# SuperCap_UPS.net
KiCad netlist of a schematic drawn in Altium Designer
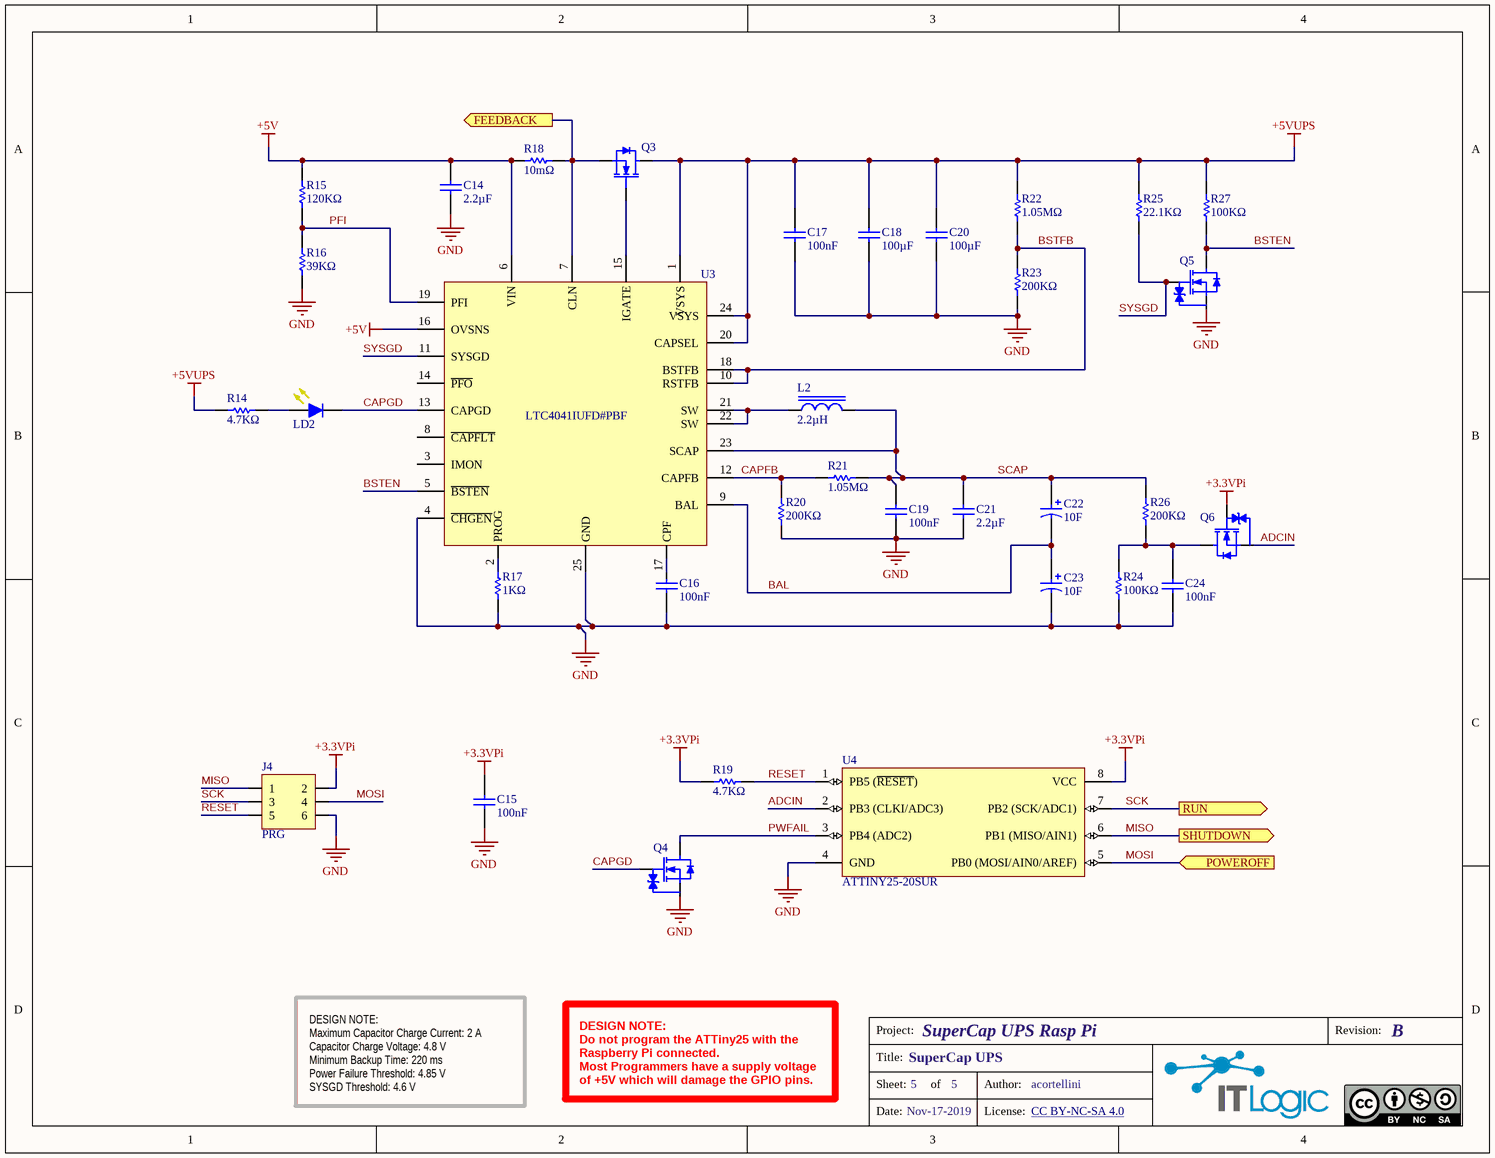
[diagram p0: SuperCap UPS.SchDoc]

(export (version "E")
  (design (tool "Eeschema 10.0.6"))
  (components
    (comp (ref "C14")
      (value "2.2µF")
      (footprint "C0805-H140")
      (description "Cap 0805 Case Ceramic 2.2uF 16V X7R 10%")
      (fields
        (field (name "MANUFACTURER") "KEMET")
        (field (name "MANUFACTURER PART NUMBER") "C0805C225K4RACTU")
      )
      (libsource (lib "IT Logic Library") (part "C0805C225K4RACTU"))
    )
    (comp (ref "C15")
      (value "100nF")
      (footprint "C0805-H10")
      (description "Cap 0805 Case Ceramic 100nF 50V X7R")
      (fields
        (field (name "MANUFACTURER") "KEMET")
        (field (name "MANUFACTURER PART NUMBER") "C0805C104K5RACTU")
      )
      (libsource (lib "IT Logic Library") (part "C0805C104K5RACTU"))
    )
    (comp (ref "C16")
      (value "100nF")
      (footprint "C0805-H10")
      (description "Cap 0805 Case Ceramic 100nF 50V X7R")
      (fields
        (field (name "MANUFACTURER") "KEMET")
        (field (name "MANUFACTURER PART NUMBER") "C0805C104K5RACTU")
      )
      (libsource (lib "IT Logic Library") (part "C0805C104K5RACTU"))
    )
    (comp (ref "C17")
      (value "100nF")
      (footprint "C0805-H10")
      (description "Cap 0805 Case Ceramic 100nF 50V X7R")
      (fields
        (field (name "MANUFACTURER") "KEMET")
        (field (name "MANUFACTURER PART NUMBER") "C0805C104K5RACTU")
      )
      (libsource (lib "IT Logic Library") (part "C0805C104K5RACTU"))
    )
    (comp (ref "C18")
      (value "100µF")
      (footprint "C1210-H250")
      (description "Cap 1210 Case Ceramic 100uF 10V X5S 20%")
      (fields
        (field (name "MANUFACTURER") "Murata")
        (field (name "MANUFACTURER PART NUMBER") "GRM32ER61A107ME20L")
      )
      (libsource (lib "IT Logic Library") (part "GRM32ER61A107ME20L"))
    )
    (comp (ref "C19")
      (value "100nF")
      (footprint "C0805-H10")
      (description "Cap 0805 Case Ceramic 100nF 50V X7R")
      (fields
        (field (name "MANUFACTURER") "KEMET")
        (field (name "MANUFACTURER PART NUMBER") "C0805C104K5RACTU")
      )
      (libsource (lib "IT Logic Library") (part "C0805C104K5RACTU"))
    )
    (comp (ref "C20")
      (value "100µF")
      (footprint "C1210-H250")
      (description "Cap 1210 Case Ceramic 100uF 10V X5S 20%")
      (fields
        (field (name "MANUFACTURER") "Murata")
        (field (name "MANUFACTURER PART NUMBER") "GRM32ER61A107ME20L")
      )
      (libsource (lib "IT Logic Library") (part "GRM32ER61A107ME20L"))
    )
    (comp (ref "C21")
      (value "2.2µF")
      (footprint "C0805-H140")
      (description "Cap 0805 Case Ceramic 2.2uF 16V X7R 10%")
      (fields
        (field (name "MANUFACTURER") "KEMET")
        (field (name "MANUFACTURER PART NUMBER") "C0805C225K4RACTU")
      )
      (libsource (lib "IT Logic Library") (part "C0805C225K4RACTU"))
    )
    (comp (ref "C22")
      (value "10F")
      (footprint "C-SCCT20B106PRB-ORIZ")
      (description "Cap Super 10F 3.0V (20 X 12.5mm) ESR 50mOhm")
      (fields (field (name "MANUFACTURER") "AVX") (field (name "MANUFACTURER PART NUMBER") "SCCT20E106SRB"))
      (libsource (lib "IT Logic Library") (part "SCCT20E106SRB"))
    )
    (comp (ref "C23")
      (value "10F")
      (footprint "C-SCCT20B106PRB-ORIZ")
      (description "Cap Super 10F 3.0V (20 X 12.5mm) ESR 50mOhm")
      (fields (field (name "MANUFACTURER") "AVX") (field (name "MANUFACTURER PART NUMBER") "SCCT20E106SRB"))
      (libsource (lib "IT Logic Library") (part "SCCT20E106SRB"))
    )
    (comp (ref "C24")
      (value "100nF")
      (footprint "C0805-H10")
      (description "Cap 0805 Case Ceramic 100nF 50V X7R")
      (fields
        (field (name "MANUFACTURER") "KEMET")
        (field (name "MANUFACTURER PART NUMBER") "C0805C104K5RACTU")
      )
      (libsource (lib "IT Logic Library") (part "C0805C104K5RACTU"))
    )
    (comp (ref "J4")
      (value "PRG")
      (footprint "HDR-V-2R-03P-5.8L")
      (description "Breakaway Header Vert - 2 Row - 3 Pos - 6 mm Lenght - Gold")
      (fields
        (field (name "MANUFACTURER") "TE Connectivity")
        (field (name "MANUFACTURER PART NUMBER") "5-146256-3")
      )
      (libsource (lib "IT Logic Library") (part "5-146256-3"))
    )
    (comp (ref "L2")
      (value "2.2µH")
      (footprint "IND-XAL5030")
      (description "Inductor Power SRP6540 Series, 2.2uH, 9.7A,  Shielded, 0.0132 ohm, SMD")
      (fields
        (field (name "MANUFACTURER") "Coilcraft")
        (field (name "MANUFACTURER PART NUMBER") "XAL5030-222MEB")
      )
      (libsource (lib "IT Logic Library") (part "XAL5030-222MEB"))
    )
    (comp (ref "LD2")
      (value "LTST-S220KSKT")
      (footprint "LED-0805-Y-SIDE")
      (description "LED 0805 Side Yellow 588nm 2-Pin")
      (fields (field (name "MANUFACTURER") "Vishay Lite-On"))
      (libsource (lib "IT Logic Library") (part "LTST-S220KSKT"))
    )
    (comp (ref "Q3")
      (value "SISA88DN-T1-GE3")
      (footprint "POWERPAK-1212-8-S")
      (description "Mosfet 30V Vds 20V Vgs 5.4mOhm PowerPAK 1212-8")
      (fields (field (name "MANUFACTURER") "Vishay"))
      (libsource (lib "IT Logic Library") (part "SISA88DN-T1-GE3"))
    )
    (comp (ref "Q4")
      (value "BSS138K-13")
      (footprint "SOT-23")
      (description "Mosfet N 50V Vds 20V Vgs ESD 1.4R SOT-23")
      (fields (field (name "MANUFACTURER") "Diodes"))
      (libsource (lib "IT Logic Library") (part "BSS138K-13"))
    )
    (comp (ref "Q5")
      (value "BSS138K-13")
      (footprint "SOT-23")
      (description "Mosfet N 50V Vds 20V Vgs ESD 1.4R SOT-23")
      (fields (field (name "MANUFACTURER") "Diodes"))
      (libsource (lib "IT Logic Library") (part "BSS138K-13"))
    )
    (comp (ref "Q6")
      (value "BSS138K-13")
      (footprint "SOT-23")
      (description "Mosfet N 50V Vds 20V Vgs ESD 1.4R SOT-23")
      (fields (field (name "MANUFACTURER") "Diodes"))
      (libsource (lib "IT Logic Library") (part "BSS138K-13"))
    )
    (comp (ref "R14")
      (value "4.7KΩ")
      (footprint "R0805-H60")
      (description "Resistor 0805 Case 4.7KR 1% 1/8W")
      (fields
        (field (name "MANUFACTURER") "Yageo")
        (field (name "MANUFACTURER PART NUMBER") "RC0805FR-074K7L")
      )
      (libsource (lib "IT Logic Library") (part "RC0805FR-074K7L"))
    )
    (comp (ref "R15")
      (value "120KΩ")
      (footprint "R0805-H60")
      (description "Resistor 0805 Case 120KR 1% 1/8W")
      (fields
        (field (name "MANUFACTURER") "Yageo")
        (field (name "MANUFACTURER PART NUMBER") "RC0805FR-07120KL")
      )
      (libsource (lib "IT Logic Library") (part "RC0805FR-07120KL"))
    )
    (comp (ref "R16")
      (value "39KΩ")
      (footprint "R0805-H60")
      (description "Resistor 0805 Case 39KR 1% 1/8W")
      (fields
        (field (name "MANUFACTURER") "Yageo")
        (field (name "MANUFACTURER PART NUMBER") "RC0805FR-0739KL")
      )
      (libsource (lib "IT Logic Library") (part "RC0805FR-0739KL"))
    )
    (comp (ref "R17")
      (value "1KΩ")
      (footprint "R0805-H60")
      (description "Resistor 0805 Case 1KR 1% 1/8W")
      (fields
        (field (name "MANUFACTURER") "Yageo")
        (field (name "MANUFACTURER PART NUMBER") "RC0805FR-071KL")
      )
      (libsource (lib "IT Logic Library") (part "RC0805FR-071KL"))
    )
    (comp (ref "R18")
      (value "10mΩ")
      (footprint "R0508-H60")
      (description "Resistor 0508 Case 10mR 1% 1/2W Current Sense")
      (fields
        (field (name "MANUFACTURER") "Susumu")
        (field (name "MANUFACTURER PART NUMBER") "KRL2012E-M-R010-F-T5")
      )
      (libsource (lib "IT Logic Library") (part "KRL2012E-M-R010-F-T5"))
    )
    (comp (ref "R19")
      (value "4.7KΩ")
      (footprint "R0805-H60")
      (description "Resistor 0805 Case 4.7KR 1% 1/8W")
      (fields
        (field (name "MANUFACTURER") "Yageo")
        (field (name "MANUFACTURER PART NUMBER") "RC0805FR-074K7L")
      )
      (libsource (lib "IT Logic Library") (part "RC0805FR-074K7L"))
    )
    (comp (ref "R20")
      (value "200KΩ")
      (footprint "R0805-H60")
      (description "Resistor 0805 Case 200KR 1% 1/8W")
      (fields
        (field (name "MANUFACTURER") "Yageo")
        (field (name "MANUFACTURER PART NUMBER") "RC0805FR-07200KL")
      )
      (libsource (lib "IT Logic Library") (part "RC0805FR-07200KL"))
    )
    (comp (ref "R21")
      (value "1.05MΩ")
      (footprint "R0805-H60")
      (description "Resistor 0805 Case 1.05MR 1% 1/8W")
      (fields
        (field (name "MANUFACTURER") "Yageo")
        (field (name "MANUFACTURER PART NUMBER") "RC0805FR-071M05L")
      )
      (libsource (lib "IT Logic Library") (part "RC0805FR-071M05L"))
    )
    (comp (ref "R22")
      (value "1.05MΩ")
      (footprint "R0805-H60")
      (description "Resistor 0805 Case 1.05MR 1% 1/8W")
      (fields
        (field (name "MANUFACTURER") "Yageo")
        (field (name "MANUFACTURER PART NUMBER") "RC0805FR-071M05L")
      )
      (libsource (lib "IT Logic Library") (part "RC0805FR-071M05L"))
    )
    (comp (ref "R23")
      (value "200KΩ")
      (footprint "R0805-H60")
      (description "Resistor 0805 Case 200KR 1% 1/8W")
      (fields
        (field (name "MANUFACTURER") "Yageo")
        (field (name "MANUFACTURER PART NUMBER") "RC0805FR-07200KL")
      )
      (libsource (lib "IT Logic Library") (part "RC0805FR-07200KL"))
    )
    (comp (ref "R24")
      (value "100KΩ")
      (footprint "R0805-H60")
      (description "Resistor 0805 Case 100KR 1% 1/8W")
      (fields
        (field (name "MANUFACTURER") "Yageo")
        (field (name "MANUFACTURER PART NUMBER") "RC0805FR-07100KL")
      )
      (libsource (lib "IT Logic Library") (part "RC0805FR-07100KL"))
    )
    (comp (ref "R25")
      (value "22.1KΩ")
      (footprint "R0805-H60")
      (description "Resistor 0805 Case 22.1KR 1% 1/8W")
      (fields
        (field (name "MANUFACTURER") "Yageo")
        (field (name "MANUFACTURER PART NUMBER") "RC0805FR-0722K1L")
      )
      (libsource (lib "IT Logic Library") (part "RC0805FR-0722K1L"))
    )
    (comp (ref "R26")
      (value "200KΩ")
      (footprint "R0805-H60")
      (description "Resistor 0805 Case 200KR 1% 1/8W")
      (fields
        (field (name "MANUFACTURER") "Yageo")
        (field (name "MANUFACTURER PART NUMBER") "RC0805FR-07200KL")
      )
      (libsource (lib "IT Logic Library") (part "RC0805FR-07200KL"))
    )
    (comp (ref "R27")
      (value "100KΩ")
      (footprint "R0805-H60")
      (description "Resistor 0805 Case 100KR 1% 1/8W")
      (fields
        (field (name "MANUFACTURER") "Yageo")
        (field (name "MANUFACTURER PART NUMBER") "RC0805FR-07100KL")
      )
      (libsource (lib "IT Logic Library") (part "RC0805FR-07100KL"))
    )
    (comp (ref "U3")
      (value "LTC4041IUFD#PBF")
      (footprint "QFN-50x40-24-THP")
      (description "Power Management 2.5A Supercapacitor Backup Buck Converter and Charger")
      (fields (field (name "MANUFACTURER") "Analog Devices"))
      (libsource (lib "IT Logic Library") (part "LTC4041IUFD#PBF"))
    )
    (comp (ref "U4")
      (value "ATTINY25-20SUR")
      (footprint "SOIC-8-W")
      (description "AVR MCU8-bit ATTiny - 2kB Flash 0.128kB EEPROM 6 I/O Pins - SOIC-8-W")
      (fields (field (name "MANUFACTURER") "Microchip"))
      (libsource (lib "IT Logic Library") (part "ATTINY25-20SUR"))
    )
  )
  (nets
    (net (code "1") (name "+3.3VPi") (class "Default")
      (node (ref "C15") (pin "2") (pinfunction "2_2") (pintype "passive"))
      (node (ref "J4") (pin "2") (pinfunction "2_2") (pintype "passive"))
      (node (ref "Q6") (pin "1") (pinfunction "G_1") (pintype "passive"))
      (node (ref "R19") (pin "1") (pinfunction "1_1") (pintype "passive"))
      (node (ref "U4") (pin "8") (pinfunction "VCC_8") (pintype "power_in"))
    )
    (net (code "2") (name "+5V") (class "Default")
      (node (ref "C14") (pin "2") (pinfunction "2_2") (pintype "passive"))
      (node (ref "R15") (pin "2") (pinfunction "2_2") (pintype "passive"))
      (node (ref "R18") (pin "1") (pinfunction "1_1") (pintype "passive"))
      (node (ref "U3") (pin "16") (pinfunction "OVSNS_16") (pintype "passive"))
      (node (ref "U3") (pin "6") (pinfunction "VIN_6") (pintype "passive"))
    )
    (net (code "3") (name "+5VUPS") (class "Default")
      (node (ref "C17") (pin "2") (pinfunction "2_2") (pintype "passive"))
      (node (ref "C18") (pin "2") (pinfunction "2_2") (pintype "passive"))
      (node (ref "C20") (pin "2") (pinfunction "2_2") (pintype "passive"))
      (node (ref "Q3") (pin "3") (pinfunction "D_3") (pintype "passive"))
      (node (ref "R14") (pin "1") (pinfunction "1_1") (pintype "passive"))
      (node (ref "R22") (pin "2") (pinfunction "2_2") (pintype "passive"))
      (node (ref "R25") (pin "2") (pinfunction "2_2") (pintype "passive"))
      (node (ref "R27") (pin "2") (pinfunction "2_2") (pintype "passive"))
      (node (ref "U3") (pin "1") (pinfunction "VSYS_1") (pintype "passive"))
      (node (ref "U3") (pin "20") (pinfunction "CAPSEL_20") (pintype "passive"))
      (node (ref "U3") (pin "24") (pinfunction "VSYS_24") (pintype "passive"))
    )
    (net (code "4") (name "/ADCIN") (class "Default")
      (node (ref "Q6") (pin "2") (pinfunction "S_2") (pintype "passive"))
      (node (ref "U4") (pin "2") (pinfunction "PB3_(CLKI/ADC3)_2") (pintype "bidirectional"))
    )
    (net (code "5") (name "/BAL") (class "Default")
      (node (ref "C22") (pin "2") (pinfunction "2_2") (pintype "passive"))
      (node (ref "C23") (pin "1") (pinfunction "1_1") (pintype "passive"))
      (node (ref "U3") (pin "9") (pinfunction "BAL_9") (pintype "passive"))
    )
    (net (code "6") (name "/BSTEN") (class "Default")
      (node (ref "Q5") (pin "3") (pinfunction "D_3") (pintype "passive"))
      (node (ref "R27") (pin "1") (pinfunction "1_1") (pintype "passive"))
      (node (ref "U3") (pin "5") (pinfunction "~{BSTEN}_5") (pintype "passive"))
    )
    (net (code "7") (name "/BSTFB") (class "Default")
      (node (ref "R22") (pin "1") (pinfunction "1_1") (pintype "passive"))
      (node (ref "R23") (pin "2") (pinfunction "2_2") (pintype "passive"))
      (node (ref "U3") (pin "10") (pinfunction "RSTFB_10") (pintype "passive"))
      (node (ref "U3") (pin "18") (pinfunction "BSTFB_18") (pintype "passive"))
    )
    (net (code "8") (name "/CAPFB") (class "Default")
      (node (ref "R20") (pin "2") (pinfunction "2_2") (pintype "passive"))
      (node (ref "R21") (pin "1") (pinfunction "1_1") (pintype "passive"))
      (node (ref "U3") (pin "12") (pinfunction "CAPFB_12") (pintype "passive"))
    )
    (net (code "9") (name "/CAPGD") (class "Default")
      (node (ref "LD2") (pin "1") (pinfunction "K_1") (pintype "passive"))
      (node (ref "Q4") (pin "1") (pinfunction "G_1") (pintype "passive"))
      (node (ref "U3") (pin "13") (pinfunction "CAPGD_13") (pintype "passive"))
    )
    (net (code "10") (name "/FEEDBACK") (class "Default")
      (node (ref "Q3") (pin "1") (pinfunction "S_1") (pintype "passive"))
      (node (ref "R18") (pin "2") (pinfunction "2_2") (pintype "passive"))
      (node (ref "U3") (pin "7") (pinfunction "CLN_7") (pintype "passive"))
    )
    (net (code "11") (name "/MISO") (class "Default")
      (node (ref "J4") (pin "1") (pinfunction "1_1") (pintype "passive"))
      (node (ref "U4") (pin "6") (pinfunction "PB1_(MISO/AIN1)_6") (pintype "bidirectional"))
    )
    (net (code "12") (name "/MOSI") (class "Default")
      (node (ref "J4") (pin "4") (pinfunction "4_4") (pintype "passive"))
      (node (ref "U4") (pin "5") (pinfunction "PB0_(MOSI/AIN0/AREF)_5") (pintype "bidirectional"))
    )
    (net (code "13") (name "/PFI") (class "Default")
      (node (ref "R15") (pin "1") (pinfunction "1_1") (pintype "passive"))
      (node (ref "R16") (pin "2") (pinfunction "2_2") (pintype "passive"))
      (node (ref "U3") (pin "19") (pinfunction "PFI_19") (pintype "passive"))
    )
    (net (code "14") (name "/PWFAIL") (class "Default")
      (node (ref "Q4") (pin "3") (pinfunction "D_3") (pintype "passive"))
      (node (ref "U4") (pin "3") (pinfunction "PB4_(ADC2)_3") (pintype "bidirectional"))
    )
    (net (code "15") (name "/RESET") (class "Default")
      (node (ref "J4") (pin "5") (pinfunction "5_5") (pintype "passive"))
      (node (ref "R19") (pin "2") (pinfunction "2_2") (pintype "passive"))
      (node (ref "U4") (pin "1") (pinfunction "PB5_(~{RESET})_1") (pintype "bidirectional"))
    )
    (net (code "16") (name "/SCAP") (class "Default")
      (node (ref "C19") (pin "2") (pinfunction "2_2") (pintype "passive"))
      (node (ref "C21") (pin "2") (pinfunction "2_2") (pintype "passive"))
      (node (ref "C22") (pin "1") (pinfunction "1_1") (pintype "passive"))
      (node (ref "L2") (pin "2") (pinfunction "2_2") (pintype "passive"))
      (node (ref "R21") (pin "2") (pinfunction "2_2") (pintype "passive"))
      (node (ref "R26") (pin "2") (pinfunction "2_2") (pintype "passive"))
      (node (ref "U3") (pin "23") (pinfunction "SCAP_23") (pintype "passive"))
    )
    (net (code "17") (name "/SCK") (class "Default")
      (node (ref "J4") (pin "3") (pinfunction "3_3") (pintype "passive"))
      (node (ref "U4") (pin "7") (pinfunction "PB2_(SCK/ADC1)_7") (pintype "bidirectional"))
    )
    (net (code "18") (name "/SYSGD") (class "Default")
      (node (ref "Q5") (pin "1") (pinfunction "G_1") (pintype "passive"))
      (node (ref "R25") (pin "1") (pinfunction "1_1") (pintype "passive"))
      (node (ref "U3") (pin "11") (pinfunction "SYSGD_11") (pintype "passive"))
    )
    (net (code "19") (name "GND") (class "Default")
      (node (ref "C14") (pin "1") (pinfunction "1_1") (pintype "passive"))
      (node (ref "C15") (pin "1") (pinfunction "1_1") (pintype "passive"))
      (node (ref "C16") (pin "1") (pinfunction "1_1") (pintype "passive"))
      (node (ref "C17") (pin "1") (pinfunction "1_1") (pintype "passive"))
      (node (ref "C18") (pin "1") (pinfunction "1_1") (pintype "passive"))
      (node (ref "C19") (pin "1") (pinfunction "1_1") (pintype "passive"))
      (node (ref "C20") (pin "1") (pinfunction "1_1") (pintype "passive"))
      (node (ref "C21") (pin "1") (pinfunction "1_1") (pintype "passive"))
      (node (ref "C23") (pin "2") (pinfunction "2_2") (pintype "passive"))
      (node (ref "C24") (pin "1") (pinfunction "1_1") (pintype "passive"))
      (node (ref "J4") (pin "6") (pinfunction "6_6") (pintype "passive"))
      (node (ref "Q4") (pin "2") (pinfunction "S_2") (pintype "passive"))
      (node (ref "Q5") (pin "2") (pinfunction "S_2") (pintype "passive"))
      (node (ref "R16") (pin "1") (pinfunction "1_1") (pintype "passive"))
      (node (ref "R17") (pin "1") (pinfunction "1_1") (pintype "passive"))
      (node (ref "R20") (pin "1") (pinfunction "1_1") (pintype "passive"))
      (node (ref "R23") (pin "1") (pinfunction "1_1") (pintype "passive"))
      (node (ref "R24") (pin "1") (pinfunction "1_1") (pintype "passive"))
      (node (ref "U3") (pin "25") (pinfunction "GND_25") (pintype "passive"))
      (node (ref "U3") (pin "4") (pinfunction "~{CHGEN}_4") (pintype "passive"))
      (node (ref "U4") (pin "4") (pinfunction "GND_4") (pintype "power_in"))
    )
    (net (code "20") (name "Net-(L2-Pad1)") (class "Default")
      (node (ref "L2") (pin "1") (pinfunction "1_1") (pintype "passive"))
      (node (ref "U3") (pin "21") (pinfunction "SW_21") (pintype "passive"))
      (node (ref "U3") (pin "22") (pinfunction "SW_22") (pintype "passive"))
    )
    (net (code "21") (name "Net-(LD2-A)") (class "Default")
      (node (ref "LD2") (pin "2") (pinfunction "A_2") (pintype "passive"))
      (node (ref "R14") (pin "2") (pinfunction "2_2") (pintype "passive"))
    )
    (net (code "22") (name "Net-(Q3-G)") (class "Default")
      (node (ref "Q3") (pin "2") (pinfunction "G_2") (pintype "passive"))
      (node (ref "U3") (pin "15") (pinfunction "IGATE_15") (pintype "passive"))
    )
    (net (code "23") (name "Net-(Q6-D)") (class "Default")
      (node (ref "C24") (pin "2") (pinfunction "2_2") (pintype "passive"))
      (node (ref "Q6") (pin "3") (pinfunction "D_3") (pintype "passive"))
      (node (ref "R24") (pin "2") (pinfunction "2_2") (pintype "passive"))
      (node (ref "R26") (pin "1") (pinfunction "1_1") (pintype "passive"))
    )
    (net (code "24") (name "Net-(U3-CPF)") (class "Default")
      (node (ref "C16") (pin "2") (pinfunction "2_2") (pintype "passive"))
      (node (ref "U3") (pin "17") (pinfunction "CPF_17") (pintype "passive"))
    )
    (net (code "25") (name "Net-(U3-PROG)") (class "Default")
      (node (ref "R17") (pin "2") (pinfunction "2_2") (pintype "passive"))
      (node (ref "U3") (pin "2") (pinfunction "PROG_2") (pintype "passive"))
    )
    (net (code "26") (name "unconnected-(U3-IMON-Pad3)") (class "Default")
      (node (ref "U3") (pin "3") (pinfunction "IMON_3") (pintype "passive"))
    )
    (net (code "27") (name "unconnected-(U3-~{CAPFLT}-Pad8)") (class "Default")
      (node (ref "U3") (pin "8") (pinfunction "~{CAPFLT}_8") (pintype "passive"))
    )
    (net (code "28") (name "unconnected-(U3-~{PFO}-Pad14)") (class "Default")
      (node (ref "U3") (pin "14") (pinfunction "~{PFO}_14") (pintype "passive"))
    )
  )
)
